# Adafruit_CyberDeck_HAT.net
KiCad netlist of a schematic drawn in EAGLE
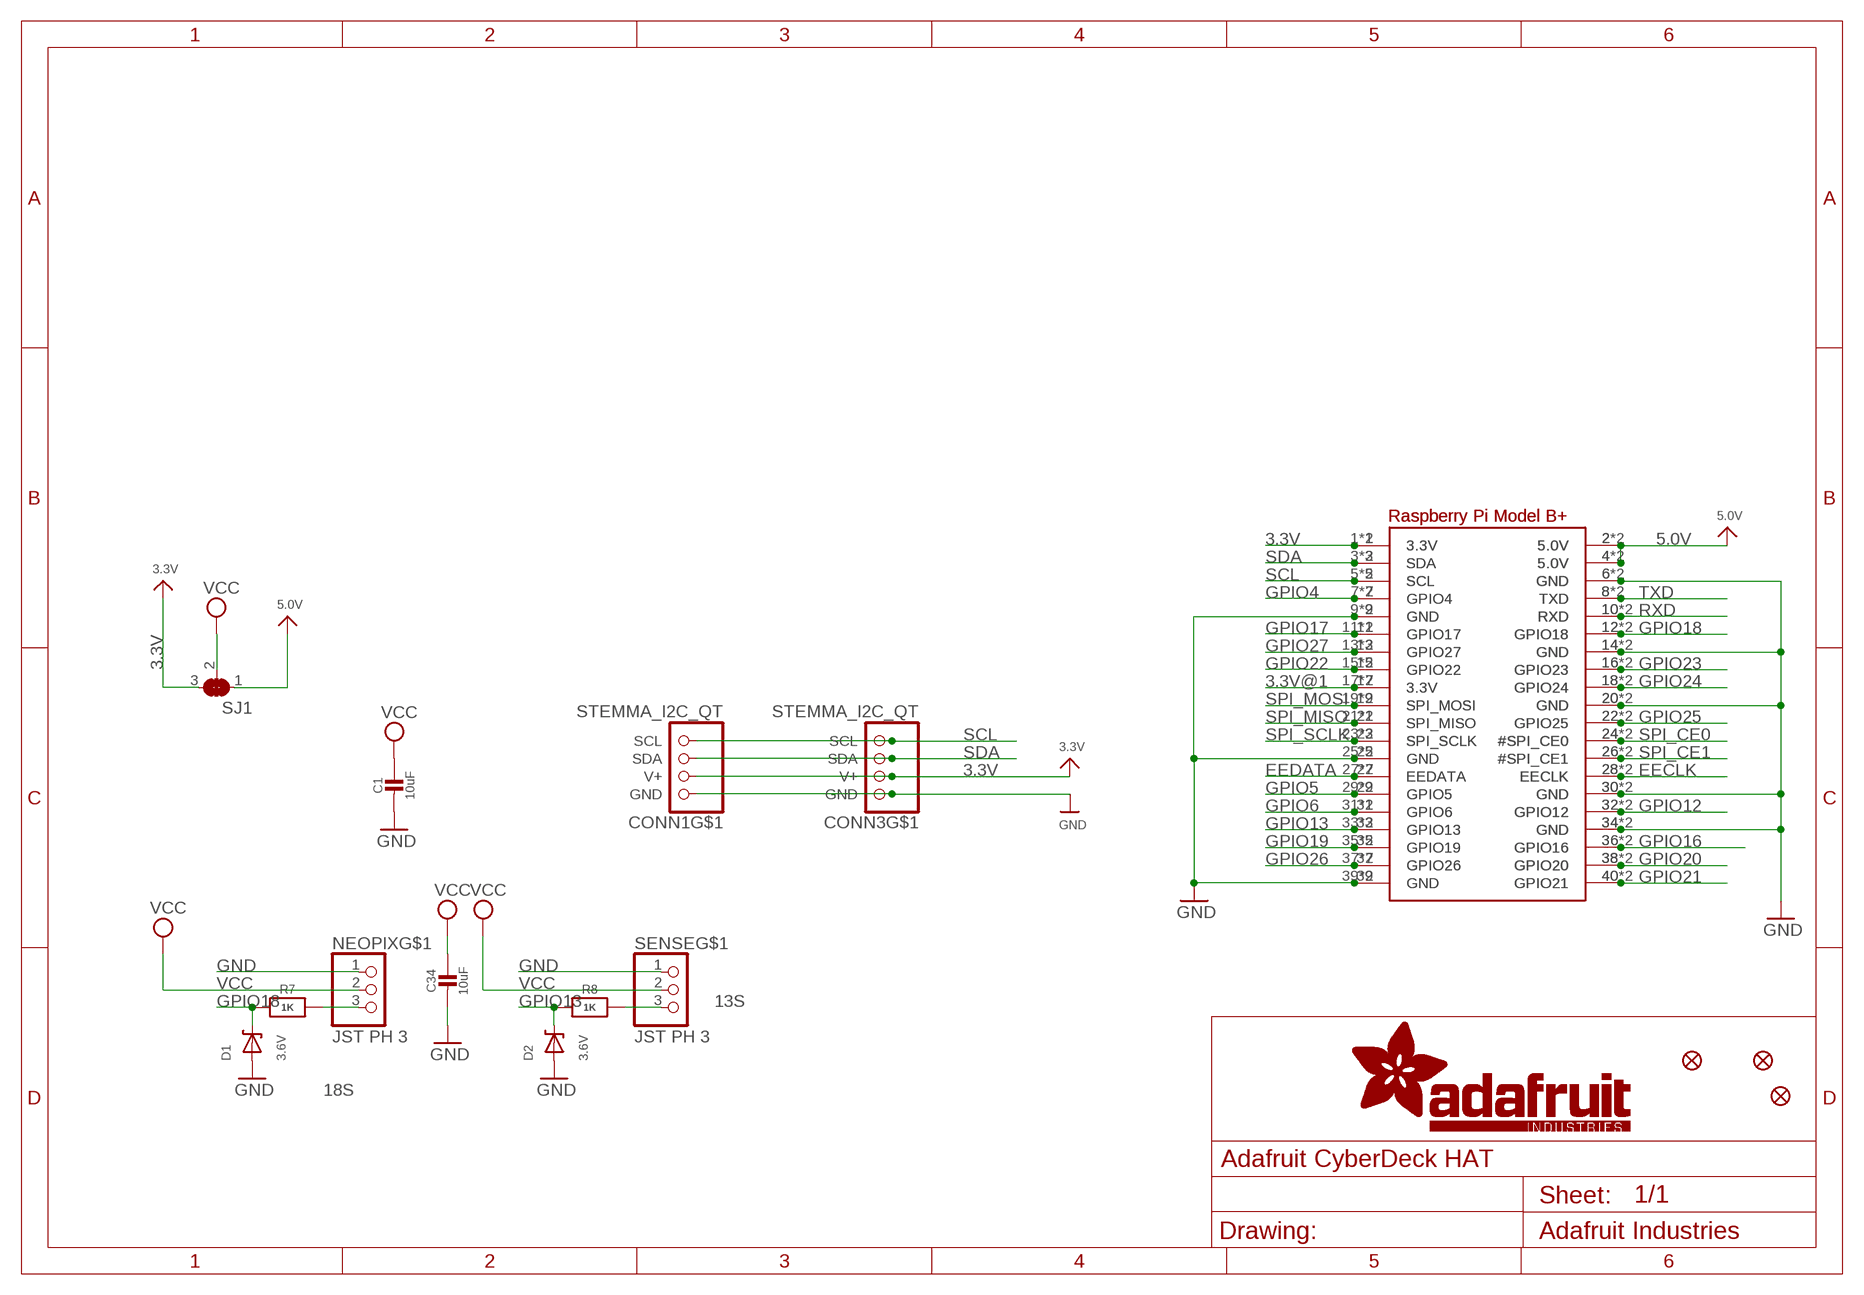
[diagram p0: schematic, sheet 1]

(export (version "E")
  (design (tool "Eeschema 10.0.6"))
  (components
    (comp (ref "C1")
      (value "10uF")
      (footprint "eagle-import:0805-NO")
      (libsource (lib "eagle-import") (part "CAP_CERAMIC0805-NOOUTLINE"))
    )
    (comp (ref "C34")
      (value "10uF")
      (footprint "eagle-import:0805-NO")
      (libsource (lib "eagle-import") (part "CAP_CERAMIC0805-NOOUTLINE"))
    )
    (comp (ref "CONN1")
      (value "STEMMA_I2C_QT")
      (footprint "eagle-import:JST_SH4")
      (libsource (lib "eagle-import") (part "STEMMA_I2C_QT"))
    )
    (comp (ref "CONN3")
      (value "STEMMA_I2C_QT")
      (footprint "eagle-import:JST_SH4")
      (libsource (lib "eagle-import") (part "STEMMA_I2C_QT"))
    )
    (comp (ref "D1")
      (value "3.6V")
      (footprint "eagle-import:SOD-323")
      (libsource (lib "eagle-import") (part "DIODE-ZENERSOD323"))
    )
    (comp (ref "D2")
      (value "3.6V")
      (footprint "eagle-import:SOD-323")
      (libsource (lib "eagle-import") (part "DIODE-ZENERSOD323"))
    )
    (comp (ref "FID1")
      (value "FIDUCIAL_1MM")
      (footprint "eagle-import:FIDUCIAL_1MM")
      (libsource (lib "eagle-import") (part "FIDUCIAL_1MM"))
    )
    (comp (ref "FID2")
      (value "FIDUCIAL_1MM")
      (footprint "eagle-import:FIDUCIAL_1MM")
      (libsource (lib "eagle-import") (part "FIDUCIAL_1MM"))
    )
    (comp (ref "FID3")
      (value "FIDUCIAL_1MM")
      (footprint "eagle-import:FIDUCIAL_1MM")
      (libsource (lib "eagle-import") (part "FIDUCIAL_1MM"))
    )
    (comp (ref "NEOPIX")
      (value "JST PH 3")
      (footprint "eagle-import:JSTPH3")
      (libsource (lib "eagle-import") (part "CON_JST_PH_3PIN"))
    )
    (comp (ref "R7")
      (value "1K")
      (footprint "eagle-import:0603-NO")
      (libsource (lib "eagle-import") (part "RESISTOR_0603_NOOUT"))
    )
    (comp (ref "R8")
      (value "1K")
      (footprint "eagle-import:0603-NO")
      (libsource (lib "eagle-import") (part "RESISTOR_0603_NOOUT"))
    )
    (comp (ref "RPI1")
      (value "RASPBERRYPI_BPLUS_IDC")
      (footprint "eagle-import:2X20")
      (libsource (lib "eagle-import") (part "RASPBERRYPI_BPLUS_IDC"))
    )
    (comp (ref "RPI3")
      (value "RASPBERRYPI_BPLUS_2X20_THMSMT_TOP")
      (footprint "eagle-import:RASPI_2X20_THMSMT_TOP")
      (libsource (lib "eagle-import") (part "RASPBERRYPI_BPLUS_2X20_THMSMT_TOP"))
    )
    (comp (ref "SENSE")
      (value "JST PH 3")
      (footprint "eagle-import:JSTPH3")
      (libsource (lib "eagle-import") (part "CON_JST_PH_3PIN"))
    )
    (comp (ref "SJ1")
      (value "SOLDERJUMPER_2WAY")
      (footprint "eagle-import:SOLDERJUMPER_2WAY_OPEN_NOPASTE")
      (libsource (lib "eagle-import") (part "SOLDERJUMPER_2WAY"))
    )
  )
  (nets
    (net (code "1") (name "/3.3V@1") (class "Default")
      (node (ref "RPI1") (pin "17") (pinfunction "3.3V_17") (pintype "power_in"))
      (node (ref "RPI3") (pin "17") (pinfunction "3.3V_17") (pintype "power_in"))
      (node (ref "RPI3") (pin "S17") (pinfunction "3.3V_S17") (pintype "power_in"))
    )
    (net (code "2") (name "/13S") (class "Default")
      (node (ref "R8") (pin "1") (pinfunction "1_1") (pintype "passive"))
      (node (ref "SENSE") (pin "3") (pinfunction "3_3") (pintype "passive"))
    )
    (net (code "3") (name "/18S") (class "Default")
      (node (ref "NEOPIX") (pin "3") (pinfunction "3_3") (pintype "passive"))
      (node (ref "R7") (pin "1") (pinfunction "1_1") (pintype "passive"))
    )
    (net (code "4") (name "/EECLK") (class "Default")
      (node (ref "RPI1") (pin "28") (pinfunction "EECLK_28") (pintype "bidirectional"))
      (node (ref "RPI3") (pin "28") (pinfunction "EECLK_28") (pintype "bidirectional"))
      (node (ref "RPI3") (pin "S28") (pinfunction "EECLK_S28") (pintype "bidirectional"))
    )
    (net (code "5") (name "/EEDATA") (class "Default")
      (node (ref "RPI1") (pin "27") (pinfunction "EEDATA_27") (pintype "bidirectional"))
      (node (ref "RPI3") (pin "27") (pinfunction "EEDATA_27") (pintype "bidirectional"))
      (node (ref "RPI3") (pin "S27") (pinfunction "EEDATA_S27") (pintype "bidirectional"))
    )
    (net (code "6") (name "/GPIO4") (class "Default")
      (node (ref "RPI1") (pin "7") (pinfunction "GPIO4_7") (pintype "bidirectional"))
      (node (ref "RPI3") (pin "7") (pinfunction "GPIO4_7") (pintype "bidirectional"))
      (node (ref "RPI3") (pin "S7") (pinfunction "GPIO4_S7") (pintype "bidirectional"))
    )
    (net (code "7") (name "/GPIO5") (class "Default")
      (node (ref "RPI1") (pin "29") (pinfunction "GPIO5_29") (pintype "bidirectional"))
      (node (ref "RPI3") (pin "29") (pinfunction "GPIO5_29") (pintype "bidirectional"))
      (node (ref "RPI3") (pin "S29") (pinfunction "GPIO5_S29") (pintype "bidirectional"))
    )
    (net (code "8") (name "/GPIO6") (class "Default")
      (node (ref "RPI1") (pin "31") (pinfunction "GPIO6_31") (pintype "bidirectional"))
      (node (ref "RPI3") (pin "31") (pinfunction "GPIO6_31") (pintype "bidirectional"))
      (node (ref "RPI3") (pin "S31") (pinfunction "GPIO6_S31") (pintype "bidirectional"))
    )
    (net (code "9") (name "/GPIO12") (class "Default")
      (node (ref "RPI1") (pin "32") (pinfunction "GPIO12_32") (pintype "bidirectional"))
      (node (ref "RPI3") (pin "32") (pinfunction "GPIO12_32") (pintype "bidirectional"))
      (node (ref "RPI3") (pin "S32") (pinfunction "GPIO12_S32") (pintype "bidirectional"))
    )
    (net (code "10") (name "/GPIO13") (class "Default")
      (node (ref "D2") (pin "C") (pinfunction "C_C") (pintype "passive"))
      (node (ref "R8") (pin "2") (pinfunction "2_2") (pintype "passive"))
      (node (ref "RPI1") (pin "33") (pinfunction "GPIO13_33") (pintype "bidirectional"))
      (node (ref "RPI3") (pin "33") (pinfunction "GPIO13_33") (pintype "bidirectional"))
      (node (ref "RPI3") (pin "S33") (pinfunction "GPIO13_S33") (pintype "bidirectional"))
    )
    (net (code "11") (name "/GPIO16") (class "Default")
      (node (ref "RPI1") (pin "36") (pinfunction "GPIO16_36") (pintype "bidirectional"))
      (node (ref "RPI3") (pin "36") (pinfunction "GPIO16_36") (pintype "bidirectional"))
      (node (ref "RPI3") (pin "S36") (pinfunction "GPIO16_S36") (pintype "bidirectional"))
    )
    (net (code "12") (name "/GPIO17") (class "Default")
      (node (ref "RPI1") (pin "11") (pinfunction "GPIO17_11") (pintype "bidirectional"))
      (node (ref "RPI3") (pin "11") (pinfunction "GPIO17_11") (pintype "bidirectional"))
      (node (ref "RPI3") (pin "S11") (pinfunction "GPIO17_S11") (pintype "bidirectional"))
    )
    (net (code "13") (name "/GPIO18") (class "Default")
      (node (ref "D1") (pin "C") (pinfunction "C_C") (pintype "passive"))
      (node (ref "R7") (pin "2") (pinfunction "2_2") (pintype "passive"))
      (node (ref "RPI1") (pin "12") (pinfunction "GPIO18_12") (pintype "bidirectional"))
      (node (ref "RPI3") (pin "12") (pinfunction "GPIO18_12") (pintype "bidirectional"))
      (node (ref "RPI3") (pin "S12") (pinfunction "GPIO18_S12") (pintype "bidirectional"))
    )
    (net (code "14") (name "/GPIO19") (class "Default")
      (node (ref "RPI1") (pin "35") (pinfunction "GPIO19_35") (pintype "bidirectional"))
      (node (ref "RPI3") (pin "35") (pinfunction "GPIO19_35") (pintype "bidirectional"))
      (node (ref "RPI3") (pin "S35") (pinfunction "GPIO19_S35") (pintype "bidirectional"))
    )
    (net (code "15") (name "/GPIO20") (class "Default")
      (node (ref "RPI1") (pin "38") (pinfunction "GPIO20_38") (pintype "bidirectional"))
      (node (ref "RPI3") (pin "38") (pinfunction "GPIO20_38") (pintype "bidirectional"))
      (node (ref "RPI3") (pin "S38") (pinfunction "GPIO20_S38") (pintype "bidirectional"))
    )
    (net (code "16") (name "/GPIO21") (class "Default")
      (node (ref "RPI1") (pin "40") (pinfunction "GPIO21_40") (pintype "bidirectional"))
      (node (ref "RPI3") (pin "40") (pinfunction "GPIO21_40") (pintype "bidirectional"))
      (node (ref "RPI3") (pin "S40") (pinfunction "GPIO21_S40") (pintype "bidirectional"))
    )
    (net (code "17") (name "/GPIO22") (class "Default")
      (node (ref "RPI1") (pin "15") (pinfunction "GPIO22_15") (pintype "bidirectional"))
      (node (ref "RPI3") (pin "15") (pinfunction "GPIO22_15") (pintype "bidirectional"))
      (node (ref "RPI3") (pin "S15") (pinfunction "GPIO22_S15") (pintype "bidirectional"))
    )
    (net (code "18") (name "/GPIO23") (class "Default")
      (node (ref "RPI1") (pin "16") (pinfunction "GPIO23_16") (pintype "bidirectional"))
      (node (ref "RPI3") (pin "16") (pinfunction "GPIO23_16") (pintype "bidirectional"))
      (node (ref "RPI3") (pin "S16") (pinfunction "GPIO23_S16") (pintype "bidirectional"))
    )
    (net (code "19") (name "/GPIO24") (class "Default")
      (node (ref "RPI1") (pin "18") (pinfunction "GPIO24_18") (pintype "bidirectional"))
      (node (ref "RPI3") (pin "18") (pinfunction "GPIO24_18") (pintype "bidirectional"))
      (node (ref "RPI3") (pin "S18") (pinfunction "GPIO24_S18") (pintype "bidirectional"))
    )
    (net (code "20") (name "/GPIO25") (class "Default")
      (node (ref "RPI1") (pin "22") (pinfunction "GPIO25_22") (pintype "bidirectional"))
      (node (ref "RPI3") (pin "22") (pinfunction "GPIO25_22") (pintype "bidirectional"))
      (node (ref "RPI3") (pin "S22") (pinfunction "GPIO25_S22") (pintype "bidirectional"))
    )
    (net (code "21") (name "/GPIO26") (class "Default")
      (node (ref "RPI1") (pin "37") (pinfunction "GPIO26_37") (pintype "bidirectional"))
      (node (ref "RPI3") (pin "37") (pinfunction "GPIO26_37") (pintype "bidirectional"))
      (node (ref "RPI3") (pin "S37") (pinfunction "GPIO26_S37") (pintype "bidirectional"))
    )
    (net (code "22") (name "/GPIO27") (class "Default")
      (node (ref "RPI1") (pin "13") (pinfunction "GPIO27_13") (pintype "bidirectional"))
      (node (ref "RPI3") (pin "13") (pinfunction "GPIO27_13") (pintype "bidirectional"))
      (node (ref "RPI3") (pin "S13") (pinfunction "GPIO27_S13") (pintype "bidirectional"))
    )
    (net (code "23") (name "/RXD") (class "Default")
      (node (ref "RPI1") (pin "10") (pinfunction "RXD_10") (pintype "bidirectional"))
      (node (ref "RPI3") (pin "10") (pinfunction "RXD_10") (pintype "bidirectional"))
      (node (ref "RPI3") (pin "S10") (pinfunction "RXD_S10") (pintype "bidirectional"))
    )
    (net (code "24") (name "/SCL") (class "Default")
      (node (ref "CONN1") (pin "4") (pinfunction "SCL_4") (pintype "passive"))
      (node (ref "CONN3") (pin "4") (pinfunction "SCL_4") (pintype "passive"))
      (node (ref "RPI1") (pin "5") (pinfunction "SCL_5") (pintype "bidirectional"))
      (node (ref "RPI3") (pin "5") (pinfunction "SCL_5") (pintype "bidirectional"))
      (node (ref "RPI3") (pin "S5") (pinfunction "SCL_S5") (pintype "bidirectional"))
    )
    (net (code "25") (name "/SDA") (class "Default")
      (node (ref "CONN1") (pin "3") (pinfunction "SDA_3") (pintype "passive"))
      (node (ref "CONN3") (pin "3") (pinfunction "SDA_3") (pintype "passive"))
      (node (ref "RPI1") (pin "3") (pinfunction "SDA_3") (pintype "bidirectional"))
      (node (ref "RPI3") (pin "3") (pinfunction "SDA_3") (pintype "bidirectional"))
      (node (ref "RPI3") (pin "S3") (pinfunction "SDA_S3") (pintype "bidirectional"))
    )
    (net (code "26") (name "/SPI_CE0") (class "Default")
      (node (ref "RPI1") (pin "24") (pinfunction "#SPI_CE0_24") (pintype "bidirectional"))
      (node (ref "RPI3") (pin "24") (pinfunction "#SPI_CE0_24") (pintype "bidirectional"))
      (node (ref "RPI3") (pin "S24") (pinfunction "#SPI_CE0_S24") (pintype "bidirectional"))
    )
    (net (code "27") (name "/SPI_CE1") (class "Default")
      (node (ref "RPI1") (pin "26") (pinfunction "#SPI_CE1_26") (pintype "bidirectional"))
      (node (ref "RPI3") (pin "26") (pinfunction "#SPI_CE1_26") (pintype "bidirectional"))
      (node (ref "RPI3") (pin "S26") (pinfunction "#SPI_CE1_S26") (pintype "bidirectional"))
    )
    (net (code "28") (name "/SPI_MISO") (class "Default")
      (node (ref "RPI1") (pin "21") (pinfunction "SPI_MISO_21") (pintype "bidirectional"))
      (node (ref "RPI3") (pin "21") (pinfunction "SPI_MISO_21") (pintype "bidirectional"))
      (node (ref "RPI3") (pin "S21") (pinfunction "SPI_MISO_S21") (pintype "bidirectional"))
    )
    (net (code "29") (name "/SPI_MOSI") (class "Default")
      (node (ref "RPI1") (pin "19") (pinfunction "SPI_MOSI_19") (pintype "bidirectional"))
      (node (ref "RPI3") (pin "19") (pinfunction "SPI_MOSI_19") (pintype "bidirectional"))
      (node (ref "RPI3") (pin "S19") (pinfunction "SPI_MOSI_S19") (pintype "bidirectional"))
    )
    (net (code "30") (name "/SPI_SCLK") (class "Default")
      (node (ref "RPI1") (pin "23") (pinfunction "SPI_SCLK_23") (pintype "bidirectional"))
      (node (ref "RPI3") (pin "23") (pinfunction "SPI_SCLK_23") (pintype "bidirectional"))
      (node (ref "RPI3") (pin "S23") (pinfunction "SPI_SCLK_S23") (pintype "bidirectional"))
    )
    (net (code "31") (name "/TXD") (class "Default")
      (node (ref "RPI1") (pin "8") (pinfunction "TXD_8") (pintype "bidirectional"))
      (node (ref "RPI3") (pin "8") (pinfunction "TXD_8") (pintype "bidirectional"))
      (node (ref "RPI3") (pin "S8") (pinfunction "TXD_S8") (pintype "bidirectional"))
    )
    (net (code "32") (name "3.3V") (class "Default")
      (node (ref "CONN1") (pin "2") (pinfunction "V+_2") (pintype "passive"))
      (node (ref "CONN3") (pin "2") (pinfunction "V+_2") (pintype "passive"))
      (node (ref "RPI1") (pin "1") (pinfunction "3.3V_1") (pintype "power_in"))
      (node (ref "RPI3") (pin "1") (pinfunction "3.3V_1") (pintype "power_in"))
      (node (ref "RPI3") (pin "S1") (pinfunction "3.3V_S1") (pintype "power_in"))
      (node (ref "SJ1") (pin "3") (pinfunction "3_3") (pintype "passive"))
    )
    (net (code "33") (name "5.0V") (class "Default")
      (node (ref "RPI1") (pin "2") (pinfunction "5.0V_2") (pintype "power_in"))
      (node (ref "RPI1") (pin "4") (pinfunction "5.0V_4") (pintype "power_in"))
      (node (ref "RPI3") (pin "2") (pinfunction "5.0V_2") (pintype "power_in"))
      (node (ref "RPI3") (pin "4") (pinfunction "5.0V_4") (pintype "power_in"))
      (node (ref "RPI3") (pin "S2") (pinfunction "5.0V_S2") (pintype "power_in"))
      (node (ref "RPI3") (pin "S4") (pinfunction "5.0V_S4") (pintype "power_in"))
      (node (ref "SJ1") (pin "1") (pinfunction "1_1") (pintype "passive"))
    )
    (net (code "34") (name "GND") (class "Default")
      (node (ref "C1") (pin "2") (pinfunction "2_2") (pintype "passive"))
      (node (ref "C34") (pin "2") (pinfunction "2_2") (pintype "passive"))
      (node (ref "CONN1") (pin "1") (pinfunction "GND_1") (pintype "passive"))
      (node (ref "CONN3") (pin "1") (pinfunction "GND_1") (pintype "passive"))
      (node (ref "D1") (pin "A") (pinfunction "A_A") (pintype "passive"))
      (node (ref "D2") (pin "A") (pinfunction "A_A") (pintype "passive"))
      (node (ref "NEOPIX") (pin "1") (pinfunction "1_1") (pintype "passive"))
      (node (ref "RPI1") (pin "14") (pinfunction "GND_14") (pintype "power_in"))
      (node (ref "RPI1") (pin "20") (pinfunction "GND_20") (pintype "power_in"))
      (node (ref "RPI1") (pin "25") (pinfunction "GND_25") (pintype "power_in"))
      (node (ref "RPI1") (pin "30") (pinfunction "GND_30") (pintype "power_in"))
      (node (ref "RPI1") (pin "34") (pinfunction "GND_34") (pintype "power_in"))
      (node (ref "RPI1") (pin "39") (pinfunction "GND_39") (pintype "power_in"))
      (node (ref "RPI1") (pin "6") (pinfunction "GND_6") (pintype "power_in"))
      (node (ref "RPI1") (pin "9") (pinfunction "GND_9") (pintype "power_in"))
      (node (ref "RPI3") (pin "14") (pinfunction "GND_14") (pintype "power_in"))
      (node (ref "RPI3") (pin "20") (pinfunction "GND_20") (pintype "power_in"))
      (node (ref "RPI3") (pin "25") (pinfunction "GND_25") (pintype "power_in"))
      (node (ref "RPI3") (pin "30") (pinfunction "GND_30") (pintype "power_in"))
      (node (ref "RPI3") (pin "34") (pinfunction "GND_34") (pintype "power_in"))
      (node (ref "RPI3") (pin "39") (pinfunction "GND_39") (pintype "power_in"))
      (node (ref "RPI3") (pin "6") (pinfunction "GND_6") (pintype "power_in"))
      (node (ref "RPI3") (pin "9") (pinfunction "GND_9") (pintype "power_in"))
      (node (ref "RPI3") (pin "S14") (pinfunction "GND_S14") (pintype "power_in"))
      (node (ref "RPI3") (pin "S20") (pinfunction "GND_S20") (pintype "power_in"))
      (node (ref "RPI3") (pin "S25") (pinfunction "GND_S25") (pintype "power_in"))
      (node (ref "RPI3") (pin "S30") (pinfunction "GND_S30") (pintype "power_in"))
      (node (ref "RPI3") (pin "S34") (pinfunction "GND_S34") (pintype "power_in"))
      (node (ref "RPI3") (pin "S39") (pinfunction "GND_S39") (pintype "power_in"))
      (node (ref "RPI3") (pin "S6") (pinfunction "GND_S6") (pintype "power_in"))
      (node (ref "RPI3") (pin "S9") (pinfunction "GND_S9") (pintype "power_in"))
      (node (ref "SENSE") (pin "1") (pinfunction "1_1") (pintype "passive"))
    )
    (net (code "35") (name "VCC") (class "Default")
      (node (ref "C1") (pin "1") (pinfunction "1_1") (pintype "passive"))
      (node (ref "C34") (pin "1") (pinfunction "1_1") (pintype "passive"))
      (node (ref "NEOPIX") (pin "2") (pinfunction "2_2") (pintype "passive"))
      (node (ref "SENSE") (pin "2") (pinfunction "2_2") (pintype "passive"))
      (node (ref "SJ1") (pin "2") (pinfunction "2_2") (pintype "passive"))
    )
  )
)
